# Projeto1.net
KiCad netlist of a schematic drawn in EAGLE
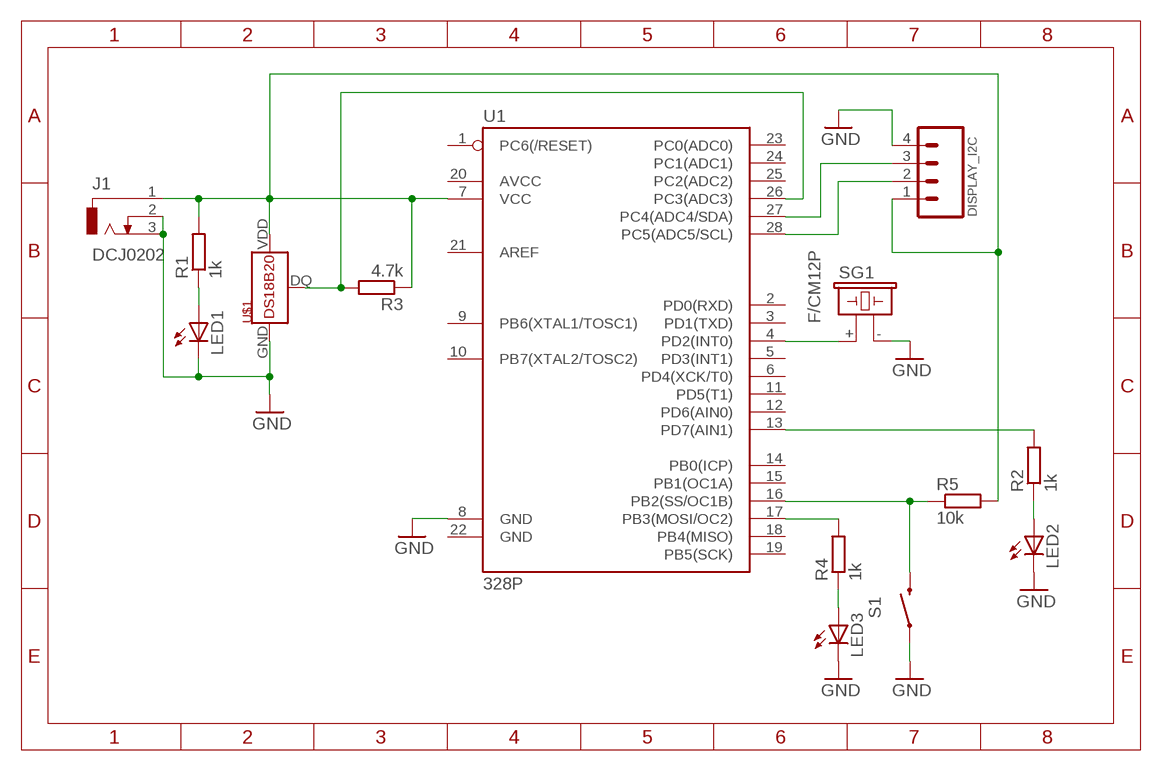
[diagram p0: schematic, sheet 1]

(export (version "E")
  (design (tool "Eeschema 10.0.6"))
  (components
    (comp (ref "DISPLAY_I2C")
      (value "MA04")
      (footprint "eagle-import:04PA")
      (libsource (lib "eagle-import") (part "MA04"))
    )
    (comp (ref "J1")
      (value "DCJ0202")
      (footprint "eagle-import:DCJ0202")
      (libsource (lib "eagle-import") (part "DCJ0202"))
    )
    (comp (ref "LED1")
      (value "LED5MM")
      (footprint "eagle-import:LED5MM")
      (libsource (lib "eagle-import") (part "LED5MM"))
    )
    (comp (ref "LED2")
      (value "LED5MM")
      (footprint "eagle-import:LED5MM")
      (libsource (lib "eagle-import") (part "LED5MM"))
    )
    (comp (ref "LED3")
      (value "LED5MM")
      (footprint "eagle-import:LED5MM")
      (libsource (lib "eagle-import") (part "LED5MM"))
    )
    (comp (ref "R1")
      (value "1k")
      (footprint "eagle-import:0204_7")
      (libsource (lib "eagle-import") (part "R-EU_0204/7"))
    )
    (comp (ref "R2")
      (value "1k")
      (footprint "eagle-import:0204_7")
      (libsource (lib "eagle-import") (part "R-EU_0204/7"))
    )
    (comp (ref "R3")
      (value "4.7k")
      (footprint "eagle-import:0204_7")
      (libsource (lib "eagle-import") (part "R-EU_0204/7"))
    )
    (comp (ref "R4")
      (value "1k")
      (footprint "eagle-import:0204_7")
      (libsource (lib "eagle-import") (part "R-EU_0204/7"))
    )
    (comp (ref "R5")
      (value "10k")
      (footprint "eagle-import:0204_7")
      (libsource (lib "eagle-import") (part "R-EU_0204/7"))
    )
    (comp (ref "S1")
      (value "MOMENTARY-SWITCH-SPST-PTH-RIGHT-ANGLE-KIT")
      (footprint "eagle-import:TACTILE_SWITCH_PTH_RIGHT_ANGLE_KIT")
      (libsource (lib "eagle-import") (part "MOMENTARY-SWITCH-SPST-PTH-RIGHT-ANGLE-KIT"))
    )
    (comp (ref "SG1")
      (value "F/CM12P")
      (footprint "eagle-import:F_CM12P")
      (libsource (lib "eagle-import") (part "F/CM12P"))
    )
    (comp (ref "U$1")
      (value "DS18B20")
      (footprint "eagle-import:TO-92")
      (libsource (lib "eagle-import") (part "DS18B20"))
    )
    (comp (ref "U1")
      (value "328P")
      (footprint "eagle-import:DIP28")
      (libsource (lib "eagle-import") (part "ATMEGA328P_PDIP"))
    )
  )
  (nets
    (net (code "1") (name "GND") (class "Default")
      (node (ref "DISPLAY_I2C") (pin "4") (pinfunction "4_4") (pintype "passive"))
      (node (ref "J1") (pin "2") (pinfunction "2_2") (pintype "passive"))
      (node (ref "J1") (pin "3") (pinfunction "3_3") (pintype "passive"))
      (node (ref "LED1") (pin "K") (pinfunction "C_K") (pintype "passive"))
      (node (ref "LED2") (pin "K") (pinfunction "C_K") (pintype "passive"))
      (node (ref "LED3") (pin "K") (pinfunction "C_K") (pintype "passive"))
      (node (ref "S1") (pin "1") (pinfunction "1_1") (pintype "passive"))
      (node (ref "SG1") (pin "-") (pinfunction "2_-") (pintype "passive"))
      (node (ref "U$1") (pin "GND") (pinfunction "1_GND") (pintype "power_in"))
      (node (ref "U1") (pin "8") (pinfunction "GND_8") (pintype "bidirectional"))
    )
    (net (code "2") (name "Net-(LED1-PadA)") (class "Default")
      (node (ref "LED1") (pin "A") (pinfunction "A_A") (pintype "passive"))
      (node (ref "R1") (pin "1") (pinfunction "1_1") (pintype "passive"))
    )
    (net (code "3") (name "Net-(LED2-PadA)") (class "Default")
      (node (ref "LED2") (pin "A") (pinfunction "A_A") (pintype "passive"))
      (node (ref "R2") (pin "1") (pinfunction "1_1") (pintype "passive"))
    )
    (net (code "4") (name "Net-(LED3-PadA)") (class "Default")
      (node (ref "LED3") (pin "A") (pinfunction "A_A") (pintype "passive"))
      (node (ref "R4") (pin "1") (pinfunction "1_1") (pintype "passive"))
    )
    (net (code "5") (name "Net-(SG1-1)") (class "Default")
      (node (ref "SG1") (pin "+") (pinfunction "1_+") (pintype "passive"))
      (node (ref "U1") (pin "4") (pinfunction "PD2(INT0)_4") (pintype "bidirectional"))
    )
    (net (code "6") (name "Net-(U$1-2)") (class "Default")
      (node (ref "R3") (pin "2") (pinfunction "2_2") (pintype "passive"))
      (node (ref "U$1") (pin "DQ") (pinfunction "2_DQ") (pintype "tri_state"))
      (node (ref "U1") (pin "26") (pinfunction "PC3(ADC3)_26") (pintype "bidirectional"))
    )
    (net (code "7") (name "Net-(U$1-3)") (class "Default")
      (node (ref "DISPLAY_I2C") (pin "1") (pinfunction "1_1") (pintype "passive"))
      (node (ref "J1") (pin "1") (pinfunction "1_1") (pintype "passive"))
      (node (ref "R1") (pin "2") (pinfunction "2_2") (pintype "passive"))
      (node (ref "R3") (pin "1") (pinfunction "1_1") (pintype "passive"))
      (node (ref "R5") (pin "2") (pinfunction "2_2") (pintype "passive"))
      (node (ref "U$1") (pin "VDD") (pinfunction "3_VDD") (pintype "power_in"))
      (node (ref "U1") (pin "7") (pinfunction "VCC_7") (pintype "bidirectional"))
    )
    (net (code "8") (name "Net-(U1-PB2(SS{slash}OC1B))") (class "Default")
      (node (ref "R5") (pin "1") (pinfunction "1_1") (pintype "passive"))
      (node (ref "S1") (pin "2") (pinfunction "2_2") (pintype "passive"))
      (node (ref "U1") (pin "16") (pinfunction "PB2(SS/OC1B)_16") (pintype "bidirectional"))
    )
    (net (code "9") (name "Net-(U1-PB3(MOSI{slash}OC2))") (class "Default")
      (node (ref "R4") (pin "2") (pinfunction "2_2") (pintype "passive"))
      (node (ref "U1") (pin "17") (pinfunction "PB3(MOSI/OC2)_17") (pintype "bidirectional"))
    )
    (net (code "10") (name "Net-(U1-PC4(ADC4{slash}SDA))") (class "Default")
      (node (ref "DISPLAY_I2C") (pin "3") (pinfunction "3_3") (pintype "passive"))
      (node (ref "U1") (pin "27") (pinfunction "PC4(ADC4/SDA)_27") (pintype "bidirectional"))
    )
    (net (code "11") (name "Net-(U1-PC5(ADC5{slash}SCL))") (class "Default")
      (node (ref "DISPLAY_I2C") (pin "2") (pinfunction "2_2") (pintype "passive"))
      (node (ref "U1") (pin "28") (pinfunction "PC5(ADC5/SCL)_28") (pintype "bidirectional"))
    )
    (net (code "12") (name "Net-(U1-PD7(AIN1))") (class "Default")
      (node (ref "R2") (pin "2") (pinfunction "2_2") (pintype "passive"))
      (node (ref "U1") (pin "13") (pinfunction "PD7(AIN1)_13") (pintype "bidirectional"))
    )
    (net (code "13") (name "unconnected-(U1-AREF-Pad21)") (class "Default")
      (node (ref "U1") (pin "21") (pinfunction "AREF_21") (pintype "bidirectional"))
    )
    (net (code "14") (name "unconnected-(U1-AVCC-Pad20)") (class "Default")
      (node (ref "U1") (pin "20") (pinfunction "AVCC_20") (pintype "bidirectional"))
    )
    (net (code "15") (name "unconnected-(U1-GND-Pad22)") (class "Default")
      (node (ref "U1") (pin "22") (pinfunction "GND_22") (pintype "bidirectional"))
    )
    (net (code "16") (name "unconnected-(U1-PB0(ICP)-Pad14)") (class "Default")
      (node (ref "U1") (pin "14") (pinfunction "PB0(ICP)_14") (pintype "bidirectional"))
    )
    (net (code "17") (name "unconnected-(U1-PB1(OC1A)-Pad15)") (class "Default")
      (node (ref "U1") (pin "15") (pinfunction "PB1(OC1A)_15") (pintype "bidirectional"))
    )
    (net (code "18") (name "unconnected-(U1-PB4(MISO)-Pad18)") (class "Default")
      (node (ref "U1") (pin "18") (pinfunction "PB4(MISO)_18") (pintype "bidirectional"))
    )
    (net (code "19") (name "unconnected-(U1-PB5(SCK)-Pad19)") (class "Default")
      (node (ref "U1") (pin "19") (pinfunction "PB5(SCK)_19") (pintype "bidirectional"))
    )
    (net (code "20") (name "unconnected-(U1-PB6(XTAL1{slash}TOSC1)-Pad9)") (class "Default")
      (node (ref "U1") (pin "9") (pinfunction "PB6(XTAL1/TOSC1)_9") (pintype "bidirectional"))
    )
    (net (code "21") (name "unconnected-(U1-PB7(XTAL2{slash}TOSC2)-Pad10)") (class "Default")
      (node (ref "U1") (pin "10") (pinfunction "PB7(XTAL2/TOSC2)_10") (pintype "bidirectional"))
    )
    (net (code "22") (name "unconnected-(U1-PC0(ADC0)-Pad23)") (class "Default")
      (node (ref "U1") (pin "23") (pinfunction "PC0(ADC0)_23") (pintype "bidirectional"))
    )
    (net (code "23") (name "unconnected-(U1-PC1(ADC1)-Pad24)") (class "Default")
      (node (ref "U1") (pin "24") (pinfunction "PC1(ADC1)_24") (pintype "bidirectional"))
    )
    (net (code "24") (name "unconnected-(U1-PC2(ADC2)-Pad25)") (class "Default")
      (node (ref "U1") (pin "25") (pinfunction "PC2(ADC2)_25") (pintype "bidirectional"))
    )
    (net (code "25") (name "unconnected-(U1-PC6({slash}RESET)-Pad1)") (class "Default")
      (node (ref "U1") (pin "1") (pinfunction "PC6(/RESET)_1") (pintype "bidirectional"))
    )
    (net (code "26") (name "unconnected-(U1-PD0(RXD)-Pad2)") (class "Default")
      (node (ref "U1") (pin "2") (pinfunction "PD0(RXD)_2") (pintype "bidirectional"))
    )
    (net (code "27") (name "unconnected-(U1-PD1(TXD)-Pad3)") (class "Default")
      (node (ref "U1") (pin "3") (pinfunction "PD1(TXD)_3") (pintype "bidirectional"))
    )
    (net (code "28") (name "unconnected-(U1-PD3(INT1)-Pad5)") (class "Default")
      (node (ref "U1") (pin "5") (pinfunction "PD3(INT1)_5") (pintype "bidirectional"))
    )
    (net (code "29") (name "unconnected-(U1-PD4(XCK{slash}T0)-Pad6)") (class "Default")
      (node (ref "U1") (pin "6") (pinfunction "PD4(XCK/T0)_6") (pintype "bidirectional"))
    )
    (net (code "30") (name "unconnected-(U1-PD5(T1)-Pad11)") (class "Default")
      (node (ref "U1") (pin "11") (pinfunction "PD5(T1)_11") (pintype "bidirectional"))
    )
    (net (code "31") (name "unconnected-(U1-PD6(AIN0)-Pad12)") (class "Default")
      (node (ref "U1") (pin "12") (pinfunction "PD6(AIN0)_12") (pintype "bidirectional"))
    )
  )
)
